# Sheet_1_2025-08-21.net
KiCad netlist of a schematic drawn in Altium Designer
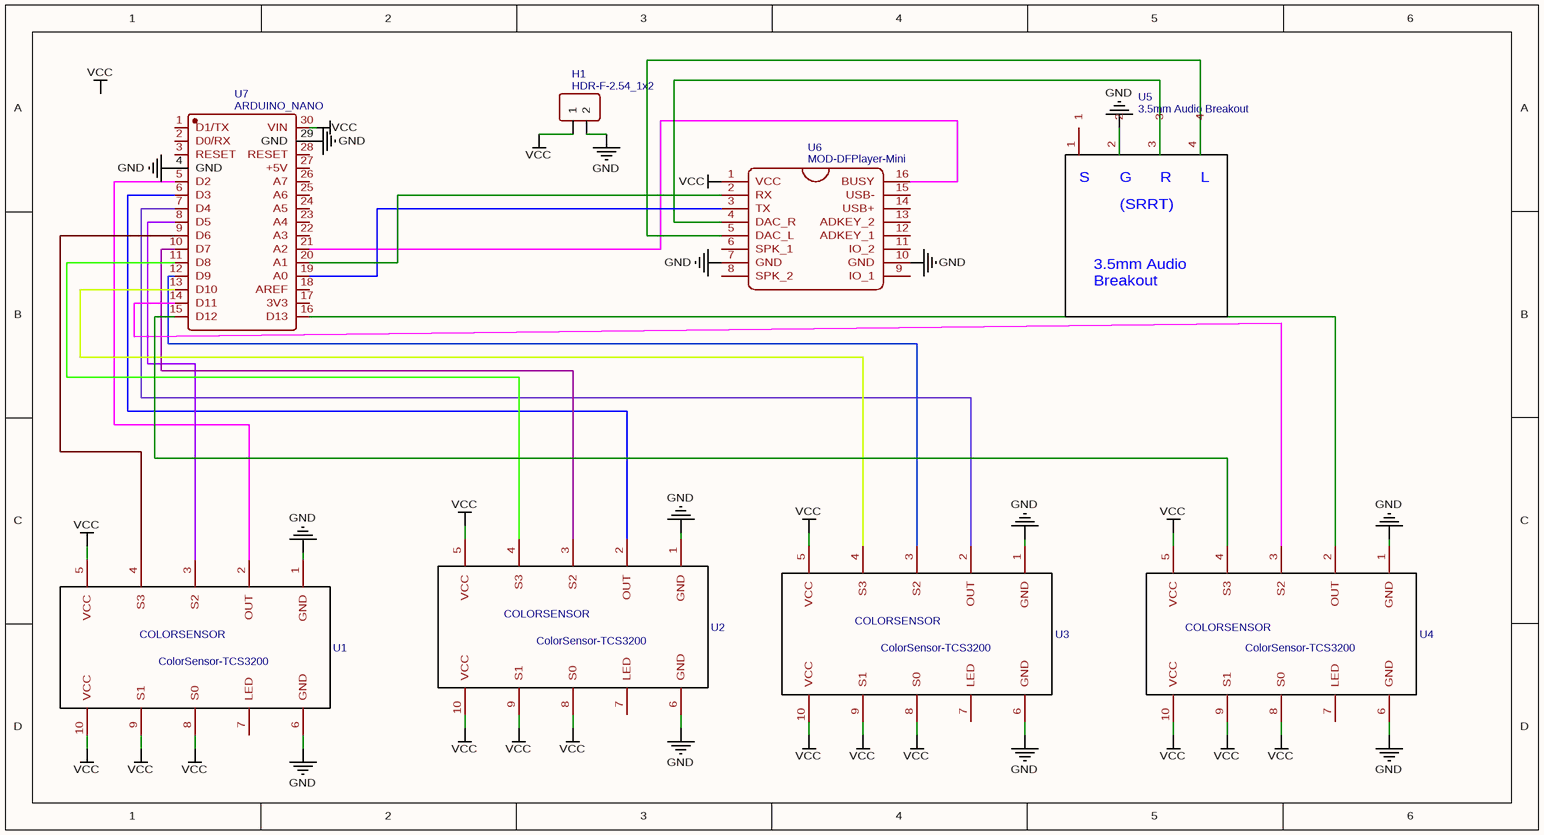
[diagram p0: Sheet_1_2025-08-21.schdoc]

(export (version "E")
  (design (tool "Eeschema 10.0.6"))
  (components
    (comp (ref "H1")
      (value "HDR-F-2.54_1x2")
      (fields (field (name "CONTRIBUTOR") "LCEDA_Lib"))
      (libsource (lib "altium-import") (part "root_1_HDR-F-2.54_1x2_"))
    )
    (comp (ref "U1")
      (value "ColorSensor-TCS3200")
      (fields (field (name "MANUFACTURER PART") "TCS230") (field (name "CONTRIBUTOR") "mahmoudd"))
      (libsource (lib "altium-import") (part "root_3_ColorSensor-TCS3200_"))
    )
    (comp (ref "U2")
      (value "ColorSensor-TCS3200")
      (fields (field (name "MANUFACTURER PART") "TCS230") (field (name "CONTRIBUTOR") "mahmoudd"))
      (libsource (lib "altium-import") (part "root_3_ColorSensor-TCS3200_"))
    )
    (comp (ref "U3")
      (value "ColorSensor-TCS3200")
      (fields (field (name "MANUFACTURER PART") "TCS230") (field (name "CONTRIBUTOR") "mahmoudd"))
      (libsource (lib "altium-import") (part "root_3_ColorSensor-TCS3200_"))
    )
    (comp (ref "U4")
      (value "ColorSensor-TCS3200")
      (fields (field (name "MANUFACTURER PART") "TCS230") (field (name "CONTRIBUTOR") "mahmoudd"))
      (libsource (lib "altium-import") (part "root_3_ColorSensor-TCS3200_"))
    )
    (comp (ref "U5")
      (value "3.5mm Audio Breakout")
      (fields (field (name "CONTRIBUTOR") "james.gruber95"))
      (libsource (lib "altium-import") (part "root_0_3.5mm Audio Breakout_"))
    )
    (comp (ref "U6")
      (value "MOD-DFPlayer-Mini")
      (fields (field (name "CONTRIBUTOR") "jackyw1368"))
      (libsource (lib "altium-import") (part "root_0_MOD-DFPlayer-Mini_"))
    )
    (comp (ref "U7")
      (value "ARDUINO_NANO")
      (fields (field (name "CONTRIBUTOR") "lcsc"))
      (libsource (lib "altium-import") (part "root_0_ARDUINO_NANO_"))
    )
  )
  (nets
    (net (code "1") (name "GND") (class "Default")
      (node (ref "H1") (pin "2") (pinfunction "2_2") (pintype "passive"))
      (node (ref "U1") (pin "1") (pinfunction "GND_1") (pintype "passive"))
      (node (ref "U1") (pin "6") (pinfunction "GND_6") (pintype "passive"))
      (node (ref "U2") (pin "1") (pinfunction "GND_1") (pintype "passive"))
      (node (ref "U2") (pin "6") (pinfunction "GND_6") (pintype "passive"))
      (node (ref "U3") (pin "1") (pinfunction "GND_1") (pintype "passive"))
      (node (ref "U3") (pin "6") (pinfunction "GND_6") (pintype "passive"))
      (node (ref "U4") (pin "1") (pinfunction "GND_1") (pintype "passive"))
      (node (ref "U4") (pin "6") (pinfunction "GND_6") (pintype "passive"))
      (node (ref "U5") (pin "2") (pinfunction "2_2") (pintype "passive"))
      (node (ref "U6") (pin "10") (pinfunction "GND_10") (pintype "passive"))
      (node (ref "U6") (pin "7") (pinfunction "GND_7") (pintype "passive"))
      (node (ref "U7") (pin "29") (pinfunction "GND_29") (pintype "passive"))
      (node (ref "U7") (pin "4") (pinfunction "GND_4") (pintype "passive"))
    )
    (net (code "2") (name "Net-(U1-OUT)") (class "Default")
      (node (ref "U1") (pin "2") (pinfunction "OUT_2") (pintype "passive"))
      (node (ref "U7") (pin "5") (pinfunction "D2_5") (pintype "passive"))
    )
    (net (code "3") (name "Net-(U1-S2)") (class "Default")
      (node (ref "U1") (pin "3") (pinfunction "S2_3") (pintype "passive"))
      (node (ref "U7") (pin "8") (pinfunction "D5_8") (pintype "passive"))
    )
    (net (code "4") (name "Net-(U1-S3)") (class "Default")
      (node (ref "U1") (pin "4") (pinfunction "S3_4") (pintype "passive"))
      (node (ref "U7") (pin "9") (pinfunction "D6_9") (pintype "passive"))
    )
    (net (code "5") (name "Net-(U2-OUT)") (class "Default")
      (node (ref "U2") (pin "2") (pinfunction "OUT_2") (pintype "passive"))
      (node (ref "U7") (pin "6") (pinfunction "D3_6") (pintype "passive"))
    )
    (net (code "6") (name "Net-(U2-S2)") (class "Default")
      (node (ref "U2") (pin "3") (pinfunction "S2_3") (pintype "passive"))
      (node (ref "U7") (pin "10") (pinfunction "D7_10") (pintype "passive"))
    )
    (net (code "7") (name "Net-(U2-S3)") (class "Default")
      (node (ref "U2") (pin "4") (pinfunction "S3_4") (pintype "passive"))
      (node (ref "U7") (pin "11") (pinfunction "D8_11") (pintype "passive"))
    )
    (net (code "8") (name "Net-(U3-OUT)") (class "Default")
      (node (ref "U3") (pin "2") (pinfunction "OUT_2") (pintype "passive"))
      (node (ref "U7") (pin "7") (pinfunction "D4_7") (pintype "passive"))
    )
    (net (code "9") (name "Net-(U3-S2)") (class "Default")
      (node (ref "U3") (pin "3") (pinfunction "S2_3") (pintype "passive"))
      (node (ref "U7") (pin "12") (pinfunction "D9_12") (pintype "passive"))
    )
    (net (code "10") (name "Net-(U3-S3)") (class "Default")
      (node (ref "U3") (pin "4") (pinfunction "S3_4") (pintype "passive"))
      (node (ref "U7") (pin "13") (pinfunction "D10_13") (pintype "passive"))
    )
    (net (code "11") (name "Net-(U4-OUT)") (class "Default")
      (node (ref "U4") (pin "2") (pinfunction "OUT_2") (pintype "passive"))
      (node (ref "U7") (pin "16") (pinfunction "D13_16") (pintype "passive"))
    )
    (net (code "12") (name "Net-(U4-S2)") (class "Default")
      (node (ref "U4") (pin "3") (pinfunction "S2_3") (pintype "passive"))
      (node (ref "U7") (pin "14") (pinfunction "D11_14") (pintype "passive"))
    )
    (net (code "13") (name "Net-(U4-S3)") (class "Default")
      (node (ref "U4") (pin "4") (pinfunction "S3_4") (pintype "passive"))
      (node (ref "U7") (pin "15") (pinfunction "D12_15") (pintype "passive"))
    )
    (net (code "14") (name "Net-(U6-BUSY)") (class "Default")
      (node (ref "U6") (pin "16") (pinfunction "BUSY_16") (pintype "passive"))
      (node (ref "U7") (pin "21") (pinfunction "A2_21") (pintype "passive"))
    )
    (net (code "15") (name "Net-(U6-DAC_L)") (class "Default")
      (node (ref "U5") (pin "4") (pinfunction "4_4") (pintype "passive"))
      (node (ref "U6") (pin "5") (pinfunction "DAC_L_5") (pintype "passive"))
    )
    (net (code "16") (name "Net-(U6-DAC_R)") (class "Default")
      (node (ref "U5") (pin "3") (pinfunction "3_3") (pintype "passive"))
      (node (ref "U6") (pin "4") (pinfunction "DAC_R_4") (pintype "passive"))
    )
    (net (code "17") (name "Net-(U6-RX)") (class "Default")
      (node (ref "U6") (pin "2") (pinfunction "RX_2") (pintype "passive"))
      (node (ref "U7") (pin "20") (pinfunction "A1_20") (pintype "passive"))
    )
    (net (code "18") (name "Net-(U6-TX)") (class "Default")
      (node (ref "U6") (pin "3") (pinfunction "TX_3") (pintype "passive"))
      (node (ref "U7") (pin "19") (pinfunction "A0_19") (pintype "passive"))
    )
    (net (code "19") (name "VCC") (class "Default")
      (node (ref "H1") (pin "1") (pinfunction "1_1") (pintype "passive"))
      (node (ref "U1") (pin "10") (pinfunction "VCC_10") (pintype "passive"))
      (node (ref "U1") (pin "5") (pinfunction "VCC_5") (pintype "passive"))
      (node (ref "U1") (pin "8") (pinfunction "S0_8") (pintype "passive"))
      (node (ref "U1") (pin "9") (pinfunction "S1_9") (pintype "passive"))
      (node (ref "U2") (pin "10") (pinfunction "VCC_10") (pintype "passive"))
      (node (ref "U2") (pin "5") (pinfunction "VCC_5") (pintype "passive"))
      (node (ref "U2") (pin "8") (pinfunction "S0_8") (pintype "passive"))
      (node (ref "U2") (pin "9") (pinfunction "S1_9") (pintype "passive"))
      (node (ref "U3") (pin "10") (pinfunction "VCC_10") (pintype "passive"))
      (node (ref "U3") (pin "5") (pinfunction "VCC_5") (pintype "passive"))
      (node (ref "U3") (pin "8") (pinfunction "S0_8") (pintype "passive"))
      (node (ref "U3") (pin "9") (pinfunction "S1_9") (pintype "passive"))
      (node (ref "U4") (pin "10") (pinfunction "VCC_10") (pintype "passive"))
      (node (ref "U4") (pin "5") (pinfunction "VCC_5") (pintype "passive"))
      (node (ref "U4") (pin "8") (pinfunction "S0_8") (pintype "passive"))
      (node (ref "U4") (pin "9") (pinfunction "S1_9") (pintype "passive"))
      (node (ref "U6") (pin "1") (pinfunction "VCC_1") (pintype "passive"))
      (node (ref "U7") (pin "30") (pinfunction "VIN_30") (pintype "passive"))
    )
    (net (code "20") (name "unconnected-(U1-LED-Pad7)") (class "Default")
      (node (ref "U1") (pin "7") (pinfunction "LED_7") (pintype "passive"))
    )
    (net (code "21") (name "unconnected-(U2-LED-Pad7)") (class "Default")
      (node (ref "U2") (pin "7") (pinfunction "LED_7") (pintype "passive"))
    )
    (net (code "22") (name "unconnected-(U3-LED-Pad7)") (class "Default")
      (node (ref "U3") (pin "7") (pinfunction "LED_7") (pintype "passive"))
    )
    (net (code "23") (name "unconnected-(U4-LED-Pad7)") (class "Default")
      (node (ref "U4") (pin "7") (pinfunction "LED_7") (pintype "passive"))
    )
    (net (code "24") (name "unconnected-(U5-Pad1)") (class "Default")
      (node (ref "U5") (pin "1") (pinfunction "1_1") (pintype "passive"))
    )
    (net (code "25") (name "unconnected-(U6-ADKEY_1-Pad12)") (class "Default")
      (node (ref "U6") (pin "12") (pinfunction "ADKEY_1_12") (pintype "passive"))
    )
    (net (code "26") (name "unconnected-(U6-ADKEY_2-Pad13)") (class "Default")
      (node (ref "U6") (pin "13") (pinfunction "ADKEY_2_13") (pintype "passive"))
    )
    (net (code "27") (name "unconnected-(U6-IO_1-Pad9)") (class "Default")
      (node (ref "U6") (pin "9") (pinfunction "IO_1_9") (pintype "passive"))
    )
    (net (code "28") (name "unconnected-(U6-IO_2-Pad11)") (class "Default")
      (node (ref "U6") (pin "11") (pinfunction "IO_2_11") (pintype "passive"))
    )
    (net (code "29") (name "unconnected-(U6-SPK_1-Pad6)") (class "Default")
      (node (ref "U6") (pin "6") (pinfunction "SPK_1_6") (pintype "passive"))
    )
    (net (code "30") (name "unconnected-(U6-SPK_2-Pad8)") (class "Default")
      (node (ref "U6") (pin "8") (pinfunction "SPK_2_8") (pintype "passive"))
    )
    (net (code "31") (name "unconnected-(U6-USB+-Pad14)") (class "Default")
      (node (ref "U6") (pin "14") (pinfunction "USB+_14") (pintype "passive"))
    )
    (net (code "32") (name "unconnected-(U6-USB--Pad15)") (class "Default")
      (node (ref "U6") (pin "15") (pinfunction "USB-_15") (pintype "passive"))
    )
    (net (code "33") (name "unconnected-(U7-+5V-Pad27)") (class "Default")
      (node (ref "U7") (pin "27") (pinfunction "+5V_27") (pintype "passive"))
    )
    (net (code "34") (name "unconnected-(U7-3V3-Pad17)") (class "Default")
      (node (ref "U7") (pin "17") (pinfunction "3V3_17") (pintype "passive"))
    )
    (net (code "35") (name "unconnected-(U7-A3-Pad22)") (class "Default")
      (node (ref "U7") (pin "22") (pinfunction "A3_22") (pintype "passive"))
    )
    (net (code "36") (name "unconnected-(U7-A4-Pad23)") (class "Default")
      (node (ref "U7") (pin "23") (pinfunction "A4_23") (pintype "passive"))
    )
    (net (code "37") (name "unconnected-(U7-A5-Pad24)") (class "Default")
      (node (ref "U7") (pin "24") (pinfunction "A5_24") (pintype "passive"))
    )
    (net (code "38") (name "unconnected-(U7-A6-Pad25)") (class "Default")
      (node (ref "U7") (pin "25") (pinfunction "A6_25") (pintype "passive"))
    )
    (net (code "39") (name "unconnected-(U7-A7-Pad26)") (class "Default")
      (node (ref "U7") (pin "26") (pinfunction "A7_26") (pintype "passive"))
    )
    (net (code "40") (name "unconnected-(U7-AREF-Pad18)") (class "Default")
      (node (ref "U7") (pin "18") (pinfunction "AREF_18") (pintype "passive"))
    )
    (net (code "41") (name "unconnected-(U7-D0{slash}RX-Pad2)") (class "Default")
      (node (ref "U7") (pin "2") (pinfunction "D0/RX_2") (pintype "passive"))
    )
    (net (code "42") (name "unconnected-(U7-D1{slash}TX-Pad1)") (class "Default")
      (node (ref "U7") (pin "1") (pinfunction "D1/TX_1") (pintype "passive"))
    )
    (net (code "43") (name "unconnected-(U7-RESET-Pad3)") (class "Default")
      (node (ref "U7") (pin "3") (pinfunction "RESET_3") (pintype "passive"))
    )
    (net (code "44") (name "unconnected-(U7-RESET-Pad28)") (class "Default")
      (node (ref "U7") (pin "28") (pinfunction "RESET_28") (pintype "passive"))
    )
  )
)
